# top_board_v1.net
KiCad netlist of a schematic drawn in EAGLE
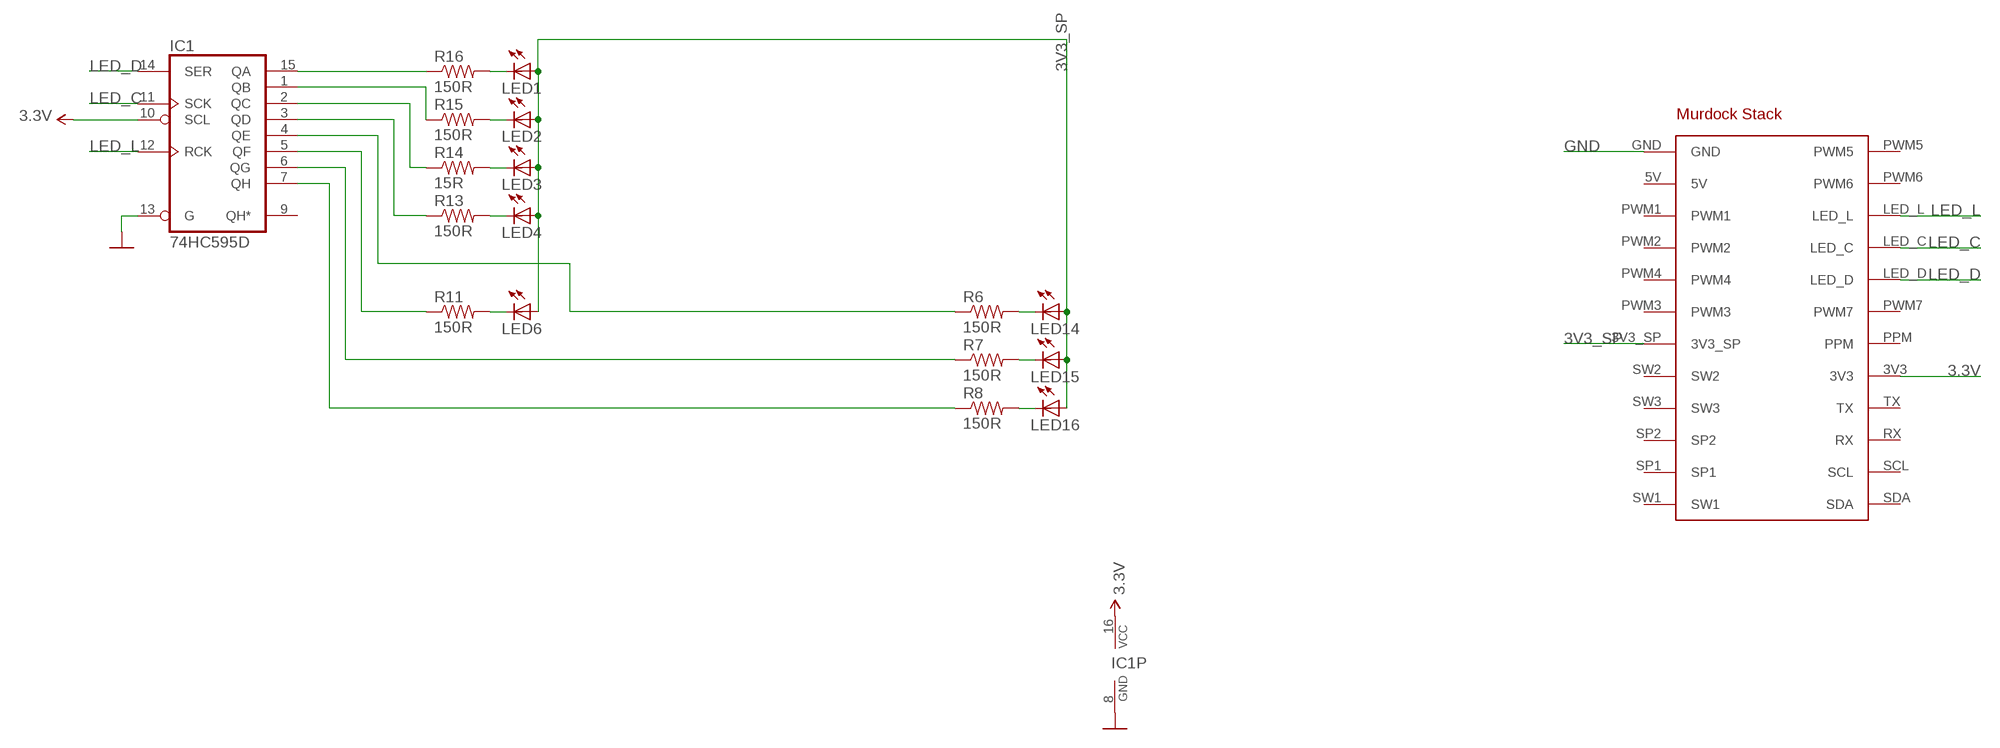
[diagram p0: schematic, sheet 1]

(export (version "E")
  (design (tool "Eeschema 10.0.6"))
  (components
    (comp (ref "IC1")
      (value "74HC595D")
      (footprint "eagle-import:SO16")
      (libsource (lib "eagle-import") (part "74595DHC"))
    )
    (comp (ref "LED1")
      (value "LGM47K")
      (footprint "eagle-import:LGM47K")
      (libsource (lib "eagle-import") (part "LGM47K"))
    )
    (comp (ref "LED2")
      (value "LGM47K")
      (footprint "eagle-import:LGM47K")
      (libsource (lib "eagle-import") (part "LGM47K"))
    )
    (comp (ref "LED3")
      (value "LGM47K")
      (footprint "eagle-import:LGM47K")
      (libsource (lib "eagle-import") (part "LGM47K"))
    )
    (comp (ref "LED4")
      (value "LGM47K")
      (footprint "eagle-import:LGM47K")
      (libsource (lib "eagle-import") (part "LGM47K"))
    )
    (comp (ref "LED6")
      (value "LGM47K")
      (footprint "eagle-import:LGM47K")
      (libsource (lib "eagle-import") (part "LGM47K"))
    )
    (comp (ref "LED14")
      (value "LGM47K")
      (footprint "eagle-import:LGM47K")
      (libsource (lib "eagle-import") (part "LGM47K"))
    )
    (comp (ref "LED15")
      (value "LGM47K")
      (footprint "eagle-import:LGM47K")
      (libsource (lib "eagle-import") (part "LGM47K"))
    )
    (comp (ref "LED16")
      (value "LGM47K")
      (footprint "eagle-import:LGM47K")
      (libsource (lib "eagle-import") (part "LGM47K"))
    )
    (comp (ref "R6")
      (value "150R")
      (footprint "eagle-import:0402-RES")
      (libsource (lib "eagle-import") (part "RESISTOR0402-RES"))
    )
    (comp (ref "R7")
      (value "150R")
      (footprint "eagle-import:0402-RES")
      (libsource (lib "eagle-import") (part "RESISTOR0402-RES"))
    )
    (comp (ref "R8")
      (value "150R")
      (footprint "eagle-import:0402-RES")
      (libsource (lib "eagle-import") (part "RESISTOR0402-RES"))
    )
    (comp (ref "R11")
      (value "150R")
      (footprint "eagle-import:0402-RES")
      (libsource (lib "eagle-import") (part "RESISTOR0402-RES"))
    )
    (comp (ref "R13")
      (value "150R")
      (footprint "eagle-import:0402-RES")
      (libsource (lib "eagle-import") (part "RESISTOR0402-RES"))
    )
    (comp (ref "R14")
      (value "15R")
      (footprint "eagle-import:0402-RES")
      (libsource (lib "eagle-import") (part "RESISTOR0402-RES"))
    )
    (comp (ref "R15")
      (value "150R")
      (footprint "eagle-import:0402-RES")
      (libsource (lib "eagle-import") (part "RESISTOR0402-RES"))
    )
    (comp (ref "R16")
      (value "150R")
      (footprint "eagle-import:0402-RES")
      (libsource (lib "eagle-import") (part "RESISTOR0402-RES"))
    )
    (comp (ref "X1")
      (value "MURDOCK_STACK")
      (footprint "eagle-import:MURDOCK_STACK")
      (libsource (lib "eagle-import") (part "MURDOCK_STACK"))
    )
  )
  (nets
    (net (code "1") (name "/3V3_SP") (class "Default")
      (node (ref "LED1") (pin "A") (pinfunction "A_A") (pintype "passive"))
      (node (ref "LED14") (pin "A") (pinfunction "A_A") (pintype "passive"))
      (node (ref "LED15") (pin "A") (pinfunction "A_A") (pintype "passive"))
      (node (ref "LED16") (pin "A") (pinfunction "A_A") (pintype "passive"))
      (node (ref "LED2") (pin "A") (pinfunction "A_A") (pintype "passive"))
      (node (ref "LED3") (pin "A") (pinfunction "A_A") (pintype "passive"))
      (node (ref "LED4") (pin "A") (pinfunction "A_A") (pintype "passive"))
      (node (ref "LED6") (pin "A") (pinfunction "A_A") (pintype "passive"))
      (node (ref "X1") (pin "3V3_SP") (pinfunction "3V3_SP_3V3_SP") (pintype "bidirectional"))
    )
    (net (code "2") (name "/LED_C") (class "Default")
      (node (ref "IC1") (pin "11") (pinfunction "SCK_11") (pintype "input"))
      (node (ref "X1") (pin "LED_C") (pinfunction "LED_C_LED_C") (pintype "bidirectional"))
    )
    (net (code "3") (name "/LED_D") (class "Default")
      (node (ref "IC1") (pin "14") (pinfunction "SER_14") (pintype "input"))
      (node (ref "X1") (pin "LED_D") (pinfunction "LED_D_LED_D") (pintype "bidirectional"))
    )
    (net (code "4") (name "/LED_L") (class "Default")
      (node (ref "IC1") (pin "12") (pinfunction "RCK_12") (pintype "input"))
      (node (ref "X1") (pin "LED_L") (pinfunction "LED_L_LED_L") (pintype "bidirectional"))
    )
    (net (code "5") (name "3.3V") (class "Default")
      (node (ref "IC1") (pin "10") (pinfunction "SCL_10") (pintype "input"))
      (node (ref "IC1") (pin "16") (pinfunction "VCC_16") (pintype "power_in"))
      (node (ref "X1") (pin "3V3") (pinfunction "3V3_3V3") (pintype "bidirectional"))
    )
    (net (code "6") (name "GND") (class "Default")
      (node (ref "IC1") (pin "13") (pinfunction "G_13") (pintype "input"))
      (node (ref "IC1") (pin "8") (pinfunction "GND_8") (pintype "power_in"))
      (node (ref "X1") (pin "GND") (pinfunction "GND_GND") (pintype "bidirectional"))
    )
    (net (code "7") (name "Net-(IC1A-QA)") (class "Default")
      (node (ref "IC1") (pin "15") (pinfunction "QA_15") (pintype "tri_state"))
      (node (ref "R16") (pin "1") (pinfunction "1_1") (pintype "passive"))
    )
    (net (code "8") (name "Net-(IC1A-QB)") (class "Default")
      (node (ref "IC1") (pin "1") (pinfunction "QB_1") (pintype "tri_state"))
      (node (ref "R15") (pin "1") (pinfunction "1_1") (pintype "passive"))
    )
    (net (code "9") (name "Net-(IC1A-QC)") (class "Default")
      (node (ref "IC1") (pin "2") (pinfunction "QC_2") (pintype "tri_state"))
      (node (ref "R14") (pin "1") (pinfunction "1_1") (pintype "passive"))
    )
    (net (code "10") (name "Net-(IC1A-QD)") (class "Default")
      (node (ref "IC1") (pin "3") (pinfunction "QD_3") (pintype "tri_state"))
      (node (ref "R13") (pin "1") (pinfunction "1_1") (pintype "passive"))
    )
    (net (code "11") (name "Net-(IC1A-QE)") (class "Default")
      (node (ref "IC1") (pin "4") (pinfunction "QE_4") (pintype "tri_state"))
      (node (ref "R6") (pin "1") (pinfunction "1_1") (pintype "passive"))
    )
    (net (code "12") (name "Net-(IC1A-QF)") (class "Default")
      (node (ref "IC1") (pin "5") (pinfunction "QF_5") (pintype "tri_state"))
      (node (ref "R11") (pin "1") (pinfunction "1_1") (pintype "passive"))
    )
    (net (code "13") (name "Net-(IC1A-QG)") (class "Default")
      (node (ref "IC1") (pin "6") (pinfunction "QG_6") (pintype "tri_state"))
      (node (ref "R7") (pin "1") (pinfunction "1_1") (pintype "passive"))
    )
    (net (code "14") (name "Net-(IC1A-QH)") (class "Default")
      (node (ref "IC1") (pin "7") (pinfunction "QH_7") (pintype "tri_state"))
      (node (ref "R8") (pin "1") (pinfunction "1_1") (pintype "passive"))
    )
    (net (code "15") (name "Net-(LED1-C)") (class "Default")
      (node (ref "LED1") (pin "K") (pinfunction "C_K") (pintype "passive"))
      (node (ref "R16") (pin "2") (pinfunction "2_2") (pintype "passive"))
    )
    (net (code "16") (name "Net-(LED2-C)") (class "Default")
      (node (ref "LED2") (pin "K") (pinfunction "C_K") (pintype "passive"))
      (node (ref "R15") (pin "2") (pinfunction "2_2") (pintype "passive"))
    )
    (net (code "17") (name "Net-(LED3-C)") (class "Default")
      (node (ref "LED3") (pin "K") (pinfunction "C_K") (pintype "passive"))
      (node (ref "R14") (pin "2") (pinfunction "2_2") (pintype "passive"))
    )
    (net (code "18") (name "Net-(LED4-C)") (class "Default")
      (node (ref "LED4") (pin "K") (pinfunction "C_K") (pintype "passive"))
      (node (ref "R13") (pin "2") (pinfunction "2_2") (pintype "passive"))
    )
    (net (code "19") (name "Net-(LED6-C)") (class "Default")
      (node (ref "LED6") (pin "K") (pinfunction "C_K") (pintype "passive"))
      (node (ref "R11") (pin "2") (pinfunction "2_2") (pintype "passive"))
    )
    (net (code "20") (name "Net-(LED14-C)") (class "Default")
      (node (ref "LED14") (pin "K") (pinfunction "C_K") (pintype "passive"))
      (node (ref "R6") (pin "2") (pinfunction "2_2") (pintype "passive"))
    )
    (net (code "21") (name "Net-(LED15-C)") (class "Default")
      (node (ref "LED15") (pin "K") (pinfunction "C_K") (pintype "passive"))
      (node (ref "R7") (pin "2") (pinfunction "2_2") (pintype "passive"))
    )
    (net (code "22") (name "Net-(LED16-C)") (class "Default")
      (node (ref "LED16") (pin "K") (pinfunction "C_K") (pintype "passive"))
      (node (ref "R8") (pin "2") (pinfunction "2_2") (pintype "passive"))
    )
    (net (code "23") (name "unconnected-(IC1A-QH*-Pad9)") (class "Default")
      (node (ref "IC1") (pin "9") (pinfunction "QH*_9") (pintype "tri_state"))
    )
    (net (code "24") (name "unconnected-(X1-Pad5V)") (class "Default")
      (node (ref "X1") (pin "5V") (pinfunction "5V_5V") (pintype "bidirectional"))
    )
    (net (code "25") (name "unconnected-(X1-PadPPM)") (class "Default")
      (node (ref "X1") (pin "PPM") (pinfunction "PPM_PPM") (pintype "bidirectional"))
    )
    (net (code "26") (name "unconnected-(X1-PadPWM1)") (class "Default")
      (node (ref "X1") (pin "PWM1") (pinfunction "PWM1_PWM1") (pintype "bidirectional"))
    )
    (net (code "27") (name "unconnected-(X1-PadPWM2)") (class "Default")
      (node (ref "X1") (pin "PWM2") (pinfunction "PWM2_PWM2") (pintype "bidirectional"))
    )
    (net (code "28") (name "unconnected-(X1-PadPWM3)") (class "Default")
      (node (ref "X1") (pin "PWM3") (pinfunction "PWM3_PWM3") (pintype "bidirectional"))
    )
    (net (code "29") (name "unconnected-(X1-PadPWM4)") (class "Default")
      (node (ref "X1") (pin "PWM4") (pinfunction "PWM4_PWM4") (pintype "bidirectional"))
    )
    (net (code "30") (name "unconnected-(X1-PadPWM5)") (class "Default")
      (node (ref "X1") (pin "PWM5") (pinfunction "PWM5_PWM5") (pintype "bidirectional"))
    )
    (net (code "31") (name "unconnected-(X1-PadPWM6)") (class "Default")
      (node (ref "X1") (pin "PWM6") (pinfunction "PWM6_PWM6") (pintype "bidirectional"))
    )
    (net (code "32") (name "unconnected-(X1-PadPWM7)") (class "Default")
      (node (ref "X1") (pin "PWM7") (pinfunction "PWM7_PWM7") (pintype "bidirectional"))
    )
    (net (code "33") (name "unconnected-(X1-PadRX)") (class "Default")
      (node (ref "X1") (pin "RX") (pinfunction "RX_RX") (pintype "bidirectional"))
    )
    (net (code "34") (name "unconnected-(X1-PadSCL)") (class "Default")
      (node (ref "X1") (pin "SCL") (pinfunction "SCL_SCL") (pintype "bidirectional"))
    )
    (net (code "35") (name "unconnected-(X1-PadSDA)") (class "Default")
      (node (ref "X1") (pin "SDA") (pinfunction "SDA_SDA") (pintype "bidirectional"))
    )
    (net (code "36") (name "unconnected-(X1-PadSP1)") (class "Default")
      (node (ref "X1") (pin "SP1") (pinfunction "SP1_SP1") (pintype "bidirectional"))
    )
    (net (code "37") (name "unconnected-(X1-PadSP2)") (class "Default")
      (node (ref "X1") (pin "SP2") (pinfunction "SP2_SP2") (pintype "bidirectional"))
    )
    (net (code "38") (name "unconnected-(X1-PadSW1)") (class "Default")
      (node (ref "X1") (pin "SW1") (pinfunction "SW1_SW1") (pintype "bidirectional"))
    )
    (net (code "39") (name "unconnected-(X1-PadSW2)") (class "Default")
      (node (ref "X1") (pin "SW2") (pinfunction "SW2_SW2") (pintype "bidirectional"))
    )
    (net (code "40") (name "unconnected-(X1-PadSW3)") (class "Default")
      (node (ref "X1") (pin "SW3") (pinfunction "SW3_SW3") (pintype "bidirectional"))
    )
    (net (code "41") (name "unconnected-(X1-PadTX)") (class "Default")
      (node (ref "X1") (pin "TX") (pinfunction "TX_TX") (pintype "bidirectional"))
    )
  )
)
